# Drive.net
KiCad netlist of a schematic drawn in Altium Designer
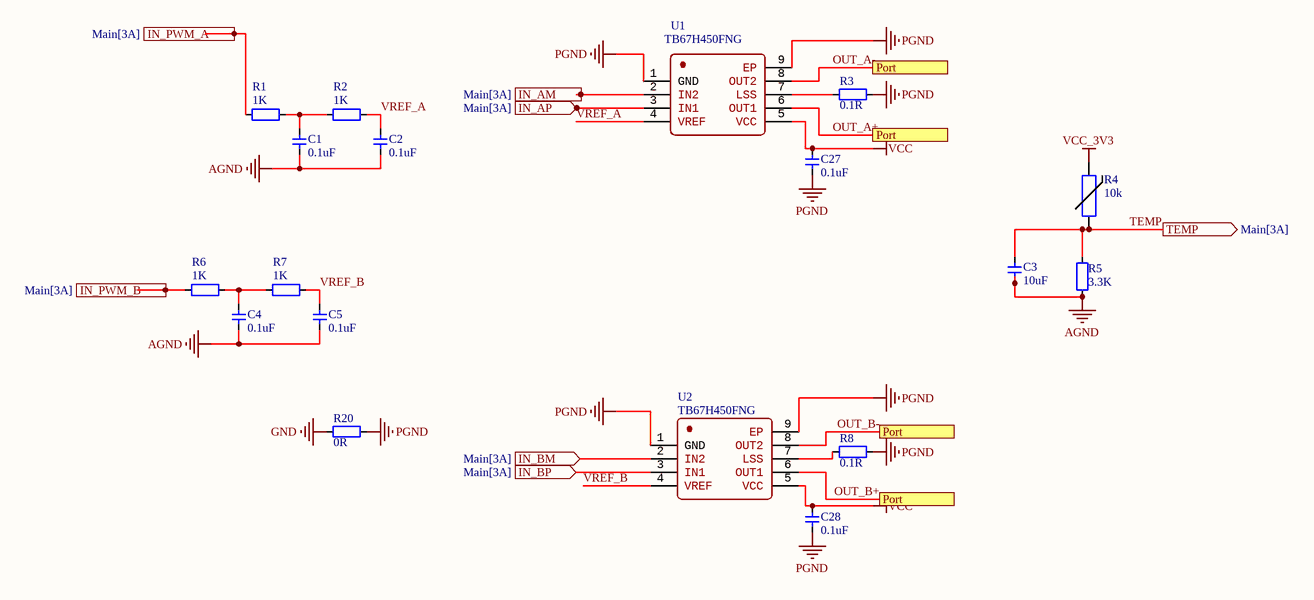
[diagram p0: Drive.SchDoc]

(export (version "E")
  (design (tool "Eeschema 10.0.6"))
  (components
    (comp (ref "C1")
      (value "0.1uF")
      (footprint "motor42-lib:CAP_0402")
      (description "Capacitor")
      (libsource (lib "MyPcbLib") (part "电容-0402"))
    )
    (comp (ref "C2")
      (value "0.1uF")
      (footprint "motor42-lib:CAP_0402")
      (description "Capacitor")
      (libsource (lib "MyPcbLib") (part "电容-0402"))
    )
    (comp (ref "C3")
      (value "10uF")
      (footprint "CAP_0402")
      (description "Capacitor")
      (libsource (lib "MyPcbLib") (part "电容-0402"))
    )
    (comp (ref "C4")
      (value "0.1uF")
      (footprint "motor42-lib:CAP_0402")
      (description "Capacitor")
      (libsource (lib "MyPcbLib") (part "电容-0402"))
    )
    (comp (ref "C5")
      (value "0.1uF")
      (footprint "motor42-lib:CAP_0402")
      (description "Capacitor")
      (libsource (lib "MyPcbLib") (part "电容-0402"))
    )
    (comp (ref "C27")
      (value "0.1uF")
      (footprint "motor42-lib:CAP_0402")
      (description "Capacitor")
      (libsource (lib "MyPcbLib") (part "电容-0402"))
    )
    (comp (ref "C28")
      (value "0.1uF")
      (footprint "motor42-lib:CAP_0402")
      (description "Capacitor")
      (libsource (lib "MyPcbLib") (part "电容-0402"))
    )
    (comp (ref "R1")
      (value "1K")
      (footprint "RES_0402")
      (description "Resistor")
      (libsource (lib "MyPcbLib") (part "电阻-0402"))
    )
    (comp (ref "R2")
      (value "1K")
      (footprint "RES_0402")
      (description "Resistor")
      (libsource (lib "MyPcbLib") (part "电阻-0402"))
    )
    (comp (ref "R3")
      (value "0.1R")
      (footprint "1206-RES")
      (description "Resistor")
      (libsource (lib "MyPcbLib") (part "电阻-1206"))
    )
    (comp (ref "R4")
      (value "10k")
      (footprint "RES_0402")
      (description "THERMISTOR 10K OHM NTC 0402 SMD")
      (fields (field (name "Comment") "NCP15XH103F03RC"))
      (libsource (lib "MyPcbLib") (part "NCP15XH103F03RC"))
    )
    (comp (ref "R5")
      (value "3.3K")
      (footprint "RES_0402")
      (description "Resistor")
      (libsource (lib "") (part "电阻-0402_1"))
    )
    (comp (ref "R6")
      (value "1K")
      (footprint "RES_0402")
      (description "Resistor")
      (libsource (lib "MyPcbLib") (part "电阻-0402"))
    )
    (comp (ref "R7")
      (value "1K")
      (footprint "RES_0402")
      (description "Resistor")
      (libsource (lib "MyPcbLib") (part "电阻-0402"))
    )
    (comp (ref "R8")
      (value "0.1R")
      (footprint "1206-RES")
      (description "Resistor")
      (libsource (lib "MyPcbLib") (part "电阻-1206"))
    )
    (comp (ref "R20")
      (value "0R")
      (footprint "1206-RES")
      (description "Resistor")
      (libsource (lib "MyPcbLib") (part "电阻-1206"))
    )
    (comp (ref "U1")
      (value "TB67H450FNG")
      (footprint "SO-8-PAD")
      (description "PWM Chopper Type DC Brushed Motor Driver")
      (libsource (lib "MyPcbLib") (part "TB67H450FNG"))
    )
    (comp (ref "U2")
      (value "TB67H450FNG")
      (footprint "SO-8-PAD")
      (description "PWM Chopper Type DC Brushed Motor Driver")
      (libsource (lib "MyPcbLib") (part "TB67H450FNG"))
    )
  )
  (nets
    (net (code "1") (name "/IN_AM") (class "Default")
      (node (ref "U1") (pin "2") (pinfunction "IN2_2") (pintype "passive"))
    )
    (net (code "2") (name "/IN_AP") (class "Default")
      (node (ref "U1") (pin "3") (pinfunction "IN1_3") (pintype "passive"))
    )
    (net (code "3") (name "/IN_BM") (class "Default")
      (node (ref "U2") (pin "2") (pinfunction "IN2_2") (pintype "passive"))
    )
    (net (code "4") (name "/IN_BP") (class "Default")
      (node (ref "U2") (pin "3") (pinfunction "IN1_3") (pintype "passive"))
    )
    (net (code "5") (name "/IN_PWM_A") (class "Default")
      (node (ref "R1") (pin "1") (pinfunction "1_1") (pintype "passive"))
    )
    (net (code "6") (name "/IN_PWM_B") (class "Default")
      (node (ref "R6") (pin "1") (pinfunction "1_1") (pintype "passive"))
    )
    (net (code "7") (name "/OUT_A+") (class "Default")
      (node (ref "U1") (pin "6") (pinfunction "OUT1_6") (pintype "passive"))
      (node (ref "U1") (pin "8") (pinfunction "OUT2_8") (pintype "passive"))
      (node (ref "U2") (pin "6") (pinfunction "OUT1_6") (pintype "passive"))
      (node (ref "U2") (pin "8") (pinfunction "OUT2_8") (pintype "passive"))
    )
    (net (code "8") (name "/TEMP") (class "Default")
      (node (ref "C3") (pin "2") (pinfunction "2_2") (pintype "passive"))
      (node (ref "R4") (pin "1") (pinfunction "0_1") (pintype "passive"))
      (node (ref "R5") (pin "2") (pinfunction "2_2") (pintype "passive"))
    )
    (net (code "9") (name "/VREF_A") (class "Default")
      (node (ref "C2") (pin "2") (pinfunction "2_2") (pintype "passive"))
      (node (ref "R2") (pin "2") (pinfunction "2_2") (pintype "passive"))
      (node (ref "U1") (pin "4") (pinfunction "VREF_4") (pintype "passive"))
    )
    (net (code "10") (name "/VREF_B") (class "Default")
      (node (ref "C5") (pin "2") (pinfunction "2_2") (pintype "passive"))
      (node (ref "R7") (pin "2") (pinfunction "2_2") (pintype "passive"))
      (node (ref "U2") (pin "4") (pinfunction "VREF_4") (pintype "passive"))
    )
    (net (code "11") (name "AGND") (class "Default")
      (node (ref "C1") (pin "1") (pinfunction "1_1") (pintype "passive"))
      (node (ref "C2") (pin "1") (pinfunction "1_1") (pintype "passive"))
      (node (ref "C3") (pin "1") (pinfunction "1_1") (pintype "passive"))
      (node (ref "C4") (pin "1") (pinfunction "1_1") (pintype "passive"))
      (node (ref "C5") (pin "1") (pinfunction "1_1") (pintype "passive"))
      (node (ref "R5") (pin "1") (pinfunction "1_1") (pintype "passive"))
    )
    (net (code "12") (name "GND") (class "Default")
      (node (ref "R20") (pin "1") (pinfunction "1_1") (pintype "passive"))
    )
    (net (code "13") (name "Net-(C1-Pad2)") (class "Default")
      (node (ref "C1") (pin "2") (pinfunction "2_2") (pintype "passive"))
      (node (ref "R1") (pin "2") (pinfunction "2_2") (pintype "passive"))
      (node (ref "R2") (pin "1") (pinfunction "1_1") (pintype "passive"))
    )
    (net (code "14") (name "Net-(C4-Pad2)") (class "Default")
      (node (ref "C4") (pin "2") (pinfunction "2_2") (pintype "passive"))
      (node (ref "R6") (pin "2") (pinfunction "2_2") (pintype "passive"))
      (node (ref "R7") (pin "1") (pinfunction "1_1") (pintype "passive"))
    )
    (net (code "15") (name "Net-(U1-LSS)") (class "Default")
      (node (ref "R3") (pin "1") (pinfunction "1_1") (pintype "passive"))
      (node (ref "U1") (pin "7") (pinfunction "LSS_7") (pintype "passive"))
    )
    (net (code "16") (name "Net-(U2-LSS)") (class "Default")
      (node (ref "R8") (pin "1") (pinfunction "1_1") (pintype "passive"))
      (node (ref "U2") (pin "7") (pinfunction "LSS_7") (pintype "passive"))
    )
    (net (code "17") (name "PGND") (class "Default")
      (node (ref "C27") (pin "1") (pinfunction "1_1") (pintype "passive"))
      (node (ref "C28") (pin "1") (pinfunction "1_1") (pintype "passive"))
      (node (ref "R20") (pin "2") (pinfunction "2_2") (pintype "passive"))
      (node (ref "R3") (pin "2") (pinfunction "2_2") (pintype "passive"))
      (node (ref "R8") (pin "2") (pinfunction "2_2") (pintype "passive"))
      (node (ref "U1") (pin "1") (pinfunction "GND_1") (pintype "passive"))
      (node (ref "U1") (pin "9") (pinfunction "EP_9") (pintype "passive"))
      (node (ref "U2") (pin "1") (pinfunction "GND_1") (pintype "passive"))
      (node (ref "U2") (pin "9") (pinfunction "EP_9") (pintype "passive"))
    )
    (net (code "18") (name "VCC") (class "Default")
      (node (ref "C27") (pin "2") (pinfunction "2_2") (pintype "passive"))
      (node (ref "C28") (pin "2") (pinfunction "2_2") (pintype "passive"))
      (node (ref "U1") (pin "5") (pinfunction "VCC_5") (pintype "passive"))
      (node (ref "U2") (pin "5") (pinfunction "VCC_5") (pintype "passive"))
    )
    (net (code "19") (name "VCC_3V3") (class "Default")
      (node (ref "R4") (pin "2") (pinfunction "0_2") (pintype "passive"))
    )
  )
)
